# -APC340.net
KiCad netlist of a schematic drawn in Altium Designer
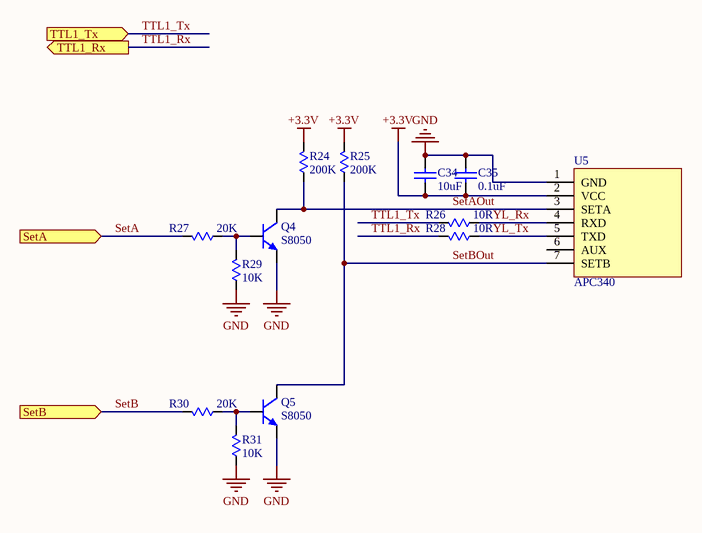
[diagram p0: 电子脚铐便携式主控板-APC340.SchDoc]

(export (version "E")
  (design (tool "Eeschema 10.0.6"))
  (components
    (comp (ref "C34")
      (value "10uF")
      (footprint "C0603")
      (description "CAP")
      (fields (field (name "PUBLISHER") "Altium Limited"))
      (libsource (lib "Passive Components Class") (part "CAP"))
    )
    (comp (ref "C35")
      (value "0.1uF")
      (footprint "C0603")
      (description "CAP")
      (fields (field (name "PUBLISHER") "Altium Limited"))
      (libsource (lib "Passive Components Class") (part "CAP"))
    )
    (comp (ref "Q4")
      (value "S8050")
      (footprint "SOT-23")
      (description "NPN triode, 0.5A Max")
      (libsource (lib "RLCYDF") (part "S8050"))
    )
    (comp (ref "Q5")
      (value "S8050")
      (footprint "SOT-23")
      (description "NPN triode, 0.5A Max")
      (libsource (lib "RLCYDF") (part "S8050"))
    )
    (comp (ref "R24")
      (value "200K")
      (footprint "R0603")
      (description "Resistor")
      (fields (field (name "PUBLISHER") "Altium Limited"))
      (libsource (lib "Passive Components Class") (part "RES"))
    )
    (comp (ref "R25")
      (value "200K")
      (footprint "R0603")
      (description "Resistor")
      (fields (field (name "PUBLISHER") "Altium Limited"))
      (libsource (lib "Passive Components Class") (part "RES"))
    )
    (comp (ref "R26")
      (value "10R")
      (footprint "R0603")
      (description "Resistor")
      (fields (field (name "Comment") "200K") (field (name "PUBLISHER") "Altium Limited"))
      (libsource (lib "Passive Components Class") (part "RES"))
    )
    (comp (ref "R27")
      (value "20K")
      (footprint "R0603")
      (description "Resistor")
      (fields (field (name "Comment") "200K") (field (name "PUBLISHER") "Altium Limited"))
      (libsource (lib "Passive Components Class") (part "RES"))
    )
    (comp (ref "R28")
      (value "10R")
      (footprint "R0603")
      (description "Resistor")
      (fields (field (name "Comment") "200K") (field (name "PUBLISHER") "Altium Limited"))
      (libsource (lib "Passive Components Class") (part "RES"))
    )
    (comp (ref "R29")
      (value "10K")
      (footprint "R0603")
      (description "Resistor")
      (fields (field (name "PUBLISHER") "Altium Limited"))
      (libsource (lib "Passive Components Class") (part "RES"))
    )
    (comp (ref "R30")
      (value "20K")
      (footprint "R0603")
      (description "Resistor")
      (fields (field (name "Comment") "200K") (field (name "PUBLISHER") "Altium Limited"))
      (libsource (lib "Passive Components Class") (part "RES"))
    )
    (comp (ref "R31")
      (value "10K")
      (footprint "R0603")
      (description "Resistor")
      (fields (field (name "PUBLISHER") "Altium Limited"))
      (libsource (lib "Passive Components Class") (part "RES"))
    )
    (comp (ref "U5") (value "APC340") (footprint "APC340") (libsource (lib "Module") (part "APC340")))
  )
  (nets
    (net (code "1") (name "+3.3V") (class "Default")
      (node (ref "C34") (pin "1") (pinfunction "1_1") (pintype "passive"))
      (node (ref "C35") (pin "1") (pinfunction "1_1") (pintype "passive"))
      (node (ref "R24") (pin "2") (pinfunction "2_2") (pintype "passive"))
      (node (ref "R25") (pin "2") (pinfunction "2_2") (pintype "passive"))
      (node (ref "U5") (pin "2") (pinfunction "VCC_2") (pintype "passive"))
    )
    (net (code "2") (name "/SetA") (class "Default")
      (node (ref "R27") (pin "2") (pinfunction "2_2") (pintype "passive"))
    )
    (net (code "3") (name "/SetAOut") (class "Default")
      (node (ref "Q4") (pin "3") (pinfunction "c_3") (pintype "passive"))
      (node (ref "R24") (pin "1") (pinfunction "1_1") (pintype "passive"))
      (node (ref "U5") (pin "3") (pinfunction "SETA_3") (pintype "passive"))
    )
    (net (code "4") (name "/SetB") (class "Default")
      (node (ref "R30") (pin "2") (pinfunction "2_2") (pintype "passive"))
    )
    (net (code "5") (name "/SetBOut") (class "Default")
      (node (ref "Q5") (pin "3") (pinfunction "c_3") (pintype "passive"))
      (node (ref "R25") (pin "1") (pinfunction "1_1") (pintype "passive"))
      (node (ref "U5") (pin "7") (pinfunction "SETB_7") (pintype "passive"))
    )
    (net (code "6") (name "/TTL1_Rx") (class "Default")
      (node (ref "R28") (pin "2") (pinfunction "2_2") (pintype "passive"))
    )
    (net (code "7") (name "/TTL1_Tx") (class "Default")
      (node (ref "R26") (pin "2") (pinfunction "2_2") (pintype "passive"))
    )
    (net (code "8") (name "/YL_Rx") (class "Default")
      (node (ref "R26") (pin "1") (pinfunction "1_1") (pintype "passive"))
      (node (ref "U5") (pin "4") (pinfunction "RXD_4") (pintype "passive"))
    )
    (net (code "9") (name "/YL_Tx") (class "Default")
      (node (ref "R28") (pin "1") (pinfunction "1_1") (pintype "passive"))
      (node (ref "U5") (pin "5") (pinfunction "TXD_5") (pintype "passive"))
    )
    (net (code "10") (name "GND") (class "Default")
      (node (ref "C34") (pin "2") (pinfunction "2_2") (pintype "passive"))
      (node (ref "C35") (pin "2") (pinfunction "2_2") (pintype "passive"))
      (node (ref "Q4") (pin "2") (pinfunction "e_2") (pintype "passive"))
      (node (ref "Q5") (pin "2") (pinfunction "e_2") (pintype "passive"))
      (node (ref "R29") (pin "1") (pinfunction "1_1") (pintype "passive"))
      (node (ref "R31") (pin "1") (pinfunction "1_1") (pintype "passive"))
      (node (ref "U5") (pin "1") (pinfunction "GND_1") (pintype "passive"))
    )
    (net (code "11") (name "Net-(Q4-b)") (class "Default")
      (node (ref "Q4") (pin "1") (pinfunction "b_1") (pintype "passive"))
      (node (ref "R27") (pin "1") (pinfunction "1_1") (pintype "passive"))
      (node (ref "R29") (pin "2") (pinfunction "2_2") (pintype "passive"))
    )
    (net (code "12") (name "Net-(Q5-b)") (class "Default")
      (node (ref "Q5") (pin "1") (pinfunction "b_1") (pintype "passive"))
      (node (ref "R30") (pin "1") (pinfunction "1_1") (pintype "passive"))
      (node (ref "R31") (pin "2") (pinfunction "2_2") (pintype "passive"))
    )
    (net (code "13") (name "unconnected-(U5-AUX-Pad6)") (class "Default")
      (node (ref "U5") (pin "6") (pinfunction "AUX_6") (pintype "passive"))
    )
  )
)
